# DashDial.net
KiCad netlist of a schematic drawn in EAGLE
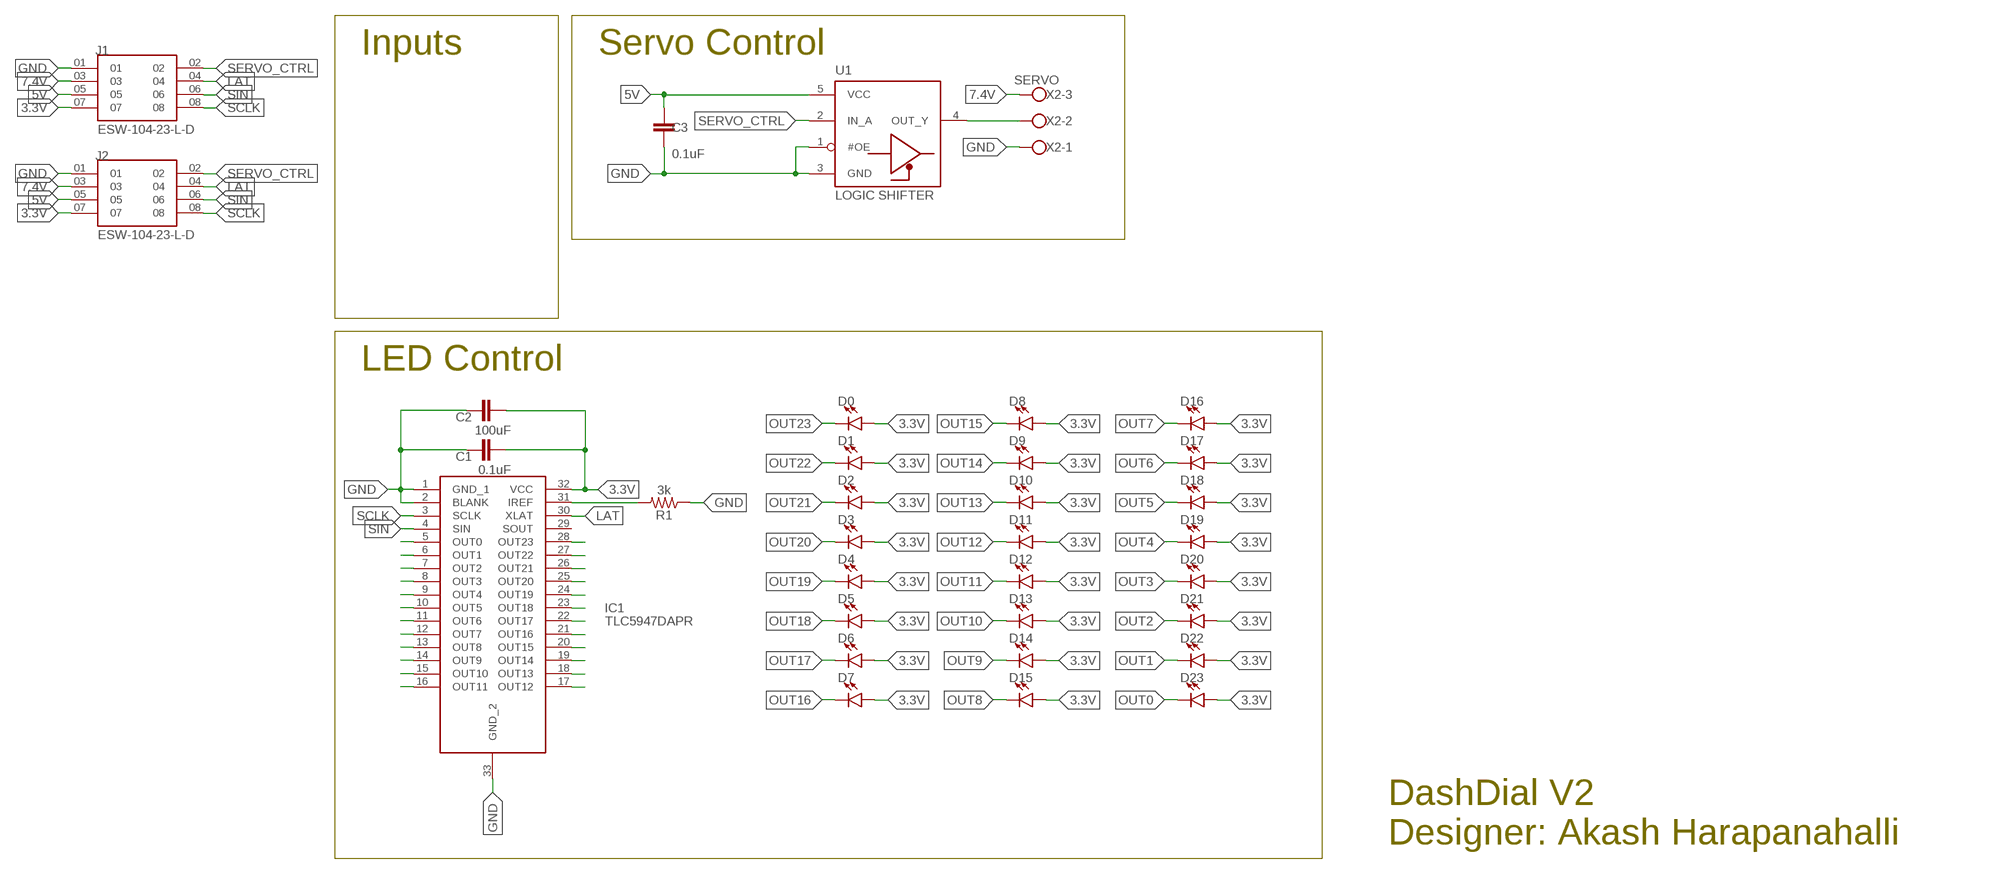
[diagram p0: schematic, sheet 1]

(export (version "E")
  (design (tool "Eeschema 10.0.6"))
  (components
    (comp (ref "C1")
      (value "0.1uF")
      (footprint "eagle-import:C0402")
      (libsource (lib "eagle-import") (part "C-EUC0402"))
    )
    (comp (ref "C2")
      (value "100uF")
      (footprint "eagle-import:C1206")
      (libsource (lib "eagle-import") (part "C-EUC1206"))
    )
    (comp (ref "C3")
      (value "0.1uF")
      (footprint "eagle-import:0603")
      (libsource (lib "eagle-import") (part "0.1UF-0603-25V-(+80/-20%)"))
    )
    (comp (ref "D0")
      (value "LED3MM")
      (footprint "eagle-import:LED_3MM")
      (libsource (lib "eagle-import") (part "LED3MM"))
    )
    (comp (ref "D1")
      (value "LED3MM")
      (footprint "eagle-import:LED_3MM")
      (libsource (lib "eagle-import") (part "LED3MM"))
    )
    (comp (ref "D2")
      (value "LED3MM")
      (footprint "eagle-import:LED_3MM")
      (libsource (lib "eagle-import") (part "LED3MM"))
    )
    (comp (ref "D3")
      (value "LED3MM")
      (footprint "eagle-import:LED_3MM")
      (libsource (lib "eagle-import") (part "LED3MM"))
    )
    (comp (ref "D4")
      (value "LED3MM")
      (footprint "eagle-import:LED_3MM")
      (libsource (lib "eagle-import") (part "LED3MM"))
    )
    (comp (ref "D5")
      (value "LED3MM")
      (footprint "eagle-import:LED_3MM")
      (libsource (lib "eagle-import") (part "LED3MM"))
    )
    (comp (ref "D6")
      (value "LED3MM")
      (footprint "eagle-import:LED_3MM")
      (libsource (lib "eagle-import") (part "LED3MM"))
    )
    (comp (ref "D7")
      (value "LED3MM")
      (footprint "eagle-import:LED_3MM")
      (libsource (lib "eagle-import") (part "LED3MM"))
    )
    (comp (ref "D8")
      (value "LED3MM")
      (footprint "eagle-import:LED_3MM")
      (libsource (lib "eagle-import") (part "LED3MM"))
    )
    (comp (ref "D9")
      (value "LED3MM")
      (footprint "eagle-import:LED_3MM")
      (libsource (lib "eagle-import") (part "LED3MM"))
    )
    (comp (ref "D10")
      (value "LED3MM")
      (footprint "eagle-import:LED_3MM")
      (libsource (lib "eagle-import") (part "LED3MM"))
    )
    (comp (ref "D11")
      (value "LED3MM")
      (footprint "eagle-import:LED_3MM")
      (libsource (lib "eagle-import") (part "LED3MM"))
    )
    (comp (ref "D12")
      (value "LED3MM")
      (footprint "eagle-import:LED_3MM")
      (libsource (lib "eagle-import") (part "LED3MM"))
    )
    (comp (ref "D13")
      (value "LED3MM")
      (footprint "eagle-import:LED_3MM")
      (libsource (lib "eagle-import") (part "LED3MM"))
    )
    (comp (ref "D14")
      (value "LED3MM")
      (footprint "eagle-import:LED_3MM")
      (libsource (lib "eagle-import") (part "LED3MM"))
    )
    (comp (ref "D15")
      (value "LED3MM")
      (footprint "eagle-import:LED_3MM")
      (libsource (lib "eagle-import") (part "LED3MM"))
    )
    (comp (ref "D16")
      (value "LED3MM")
      (footprint "eagle-import:LED_3MM")
      (libsource (lib "eagle-import") (part "LED3MM"))
    )
    (comp (ref "D17")
      (value "LED3MM")
      (footprint "eagle-import:LED_3MM")
      (libsource (lib "eagle-import") (part "LED3MM"))
    )
    (comp (ref "D18")
      (value "LED3MM")
      (footprint "eagle-import:LED_3MM")
      (libsource (lib "eagle-import") (part "LED3MM"))
    )
    (comp (ref "D19")
      (value "LED3MM")
      (footprint "eagle-import:LED_3MM")
      (libsource (lib "eagle-import") (part "LED3MM"))
    )
    (comp (ref "D20")
      (value "LED3MM")
      (footprint "eagle-import:LED_3MM")
      (libsource (lib "eagle-import") (part "LED3MM"))
    )
    (comp (ref "D21")
      (value "LED3MM")
      (footprint "eagle-import:LED_3MM")
      (libsource (lib "eagle-import") (part "LED3MM"))
    )
    (comp (ref "D22")
      (value "LED3MM")
      (footprint "eagle-import:LED_3MM")
      (libsource (lib "eagle-import") (part "LED3MM"))
    )
    (comp (ref "D23")
      (value "LED3MM")
      (footprint "eagle-import:LED_3MM")
      (libsource (lib "eagle-import") (part "LED3MM"))
    )
    (comp (ref "IC1")
      (value "TLC5947DAPR")
      (footprint "eagle-import:SOP65P810X120-33N")
      (fields (field (name "MOUSER_PART_NUMBER") "595-TLC5947DAPR"))
      (libsource (lib "eagle-import") (part "TLC5947DAPR"))
    )
    (comp (ref "J1")
      (value "ESW-104-23-L-D")
      (footprint "eagle-import:SAMTEC_ESW-104-23-L-D")
      (fields (field (name "MANUFACTURER") "Samtec Inc."))
      (libsource (lib "eagle-import") (part "ESW-104-23-L-D"))
    )
    (comp (ref "J2")
      (value "ESW-104-23-L-D")
      (footprint "eagle-import:SAMTEC_ESW-104-23-L-D")
      (fields (field (name "MANUFACTURER") "Samtec Inc."))
      (libsource (lib "eagle-import") (part "ESW-104-23-L-D"))
    )
    (comp (ref "R1")
      (value "3k")
      (footprint "eagle-import:AXIAL-0.3")
      (libsource (lib "eagle-import") (part "RESISTORAXIAL-0.3"))
    )
    (comp (ref "U1")
      (value "LOGIC SHIFTER")
      (footprint "eagle-import:SOT353")
      (fields (field (name "MF") "ON Semiconductor") (field (name "MP") "MC74VHC1GT125"))
      (libsource (lib "eagle-import") (part "MC74VHC1GT125DF"))
    )
    (comp (ref "X2")
      (value "SERVO")
      (footprint "eagle-import:W237-103")
      (fields (field (name "MPN") "237-103"))
      (libsource (lib "eagle-import") (part "W237-103"))
    )
  )
  (nets
    (net (code "1") (name "3.3V") (class "Default")
      (node (ref "C1") (pin "2") (pinfunction "2_2") (pintype "passive"))
      (node (ref "C2") (pin "2") (pinfunction "2_2") (pintype "passive"))
      (node (ref "D0") (pin "A") (pinfunction "A_A") (pintype "passive"))
      (node (ref "D1") (pin "A") (pinfunction "A_A") (pintype "passive"))
      (node (ref "D10") (pin "A") (pinfunction "A_A") (pintype "passive"))
      (node (ref "D11") (pin "A") (pinfunction "A_A") (pintype "passive"))
      (node (ref "D12") (pin "A") (pinfunction "A_A") (pintype "passive"))
      (node (ref "D13") (pin "A") (pinfunction "A_A") (pintype "passive"))
      (node (ref "D14") (pin "A") (pinfunction "A_A") (pintype "passive"))
      (node (ref "D15") (pin "A") (pinfunction "A_A") (pintype "passive"))
      (node (ref "D16") (pin "A") (pinfunction "A_A") (pintype "passive"))
      (node (ref "D17") (pin "A") (pinfunction "A_A") (pintype "passive"))
      (node (ref "D18") (pin "A") (pinfunction "A_A") (pintype "passive"))
      (node (ref "D19") (pin "A") (pinfunction "A_A") (pintype "passive"))
      (node (ref "D2") (pin "A") (pinfunction "A_A") (pintype "passive"))
      (node (ref "D20") (pin "A") (pinfunction "A_A") (pintype "passive"))
      (node (ref "D21") (pin "A") (pinfunction "A_A") (pintype "passive"))
      (node (ref "D22") (pin "A") (pinfunction "A_A") (pintype "passive"))
      (node (ref "D23") (pin "A") (pinfunction "A_A") (pintype "passive"))
      (node (ref "D3") (pin "A") (pinfunction "A_A") (pintype "passive"))
      (node (ref "D4") (pin "A") (pinfunction "A_A") (pintype "passive"))
      (node (ref "D5") (pin "A") (pinfunction "A_A") (pintype "passive"))
      (node (ref "D6") (pin "A") (pinfunction "A_A") (pintype "passive"))
      (node (ref "D7") (pin "A") (pinfunction "A_A") (pintype "passive"))
      (node (ref "D8") (pin "A") (pinfunction "A_A") (pintype "passive"))
      (node (ref "D9") (pin "A") (pinfunction "A_A") (pintype "passive"))
      (node (ref "IC1") (pin "32") (pinfunction "VCC_32") (pintype "power_in"))
      (node (ref "J1") (pin "07") (pinfunction "07_07") (pintype "passive"))
      (node (ref "J2") (pin "07") (pinfunction "07_07") (pintype "passive"))
    )
    (net (code "2") (name "5V") (class "Default")
      (node (ref "C3") (pin "1") (pinfunction "1_1") (pintype "passive"))
      (node (ref "J1") (pin "05") (pinfunction "05_05") (pintype "passive"))
      (node (ref "J2") (pin "05") (pinfunction "05_05") (pintype "passive"))
      (node (ref "U1") (pin "5") (pinfunction "VCC_5") (pintype "power_in"))
    )
    (net (code "3") (name "7.4V") (class "Default")
      (node (ref "J1") (pin "03") (pinfunction "03_03") (pintype "passive"))
      (node (ref "J2") (pin "03") (pinfunction "03_03") (pintype "passive"))
      (node (ref "X2") (pin "3") (pinfunction "KL_3") (pintype "passive"))
    )
    (net (code "4") (name "GND") (class "Default")
      (node (ref "C1") (pin "1") (pinfunction "1_1") (pintype "passive"))
      (node (ref "C2") (pin "1") (pinfunction "1_1") (pintype "passive"))
      (node (ref "C3") (pin "2") (pinfunction "2_2") (pintype "passive"))
      (node (ref "IC1") (pin "1") (pinfunction "GND_1_1") (pintype "power_in"))
      (node (ref "IC1") (pin "2") (pinfunction "BLANK_2") (pintype "input"))
      (node (ref "IC1") (pin "33") (pinfunction "GND_2_33") (pintype "power_in"))
      (node (ref "J1") (pin "01") (pinfunction "01_01") (pintype "passive"))
      (node (ref "J2") (pin "01") (pinfunction "01_01") (pintype "passive"))
      (node (ref "R1") (pin "P$1") (pinfunction "1_P$1") (pintype "passive"))
      (node (ref "U1") (pin "1") (pinfunction "#OE_1") (pintype "input"))
      (node (ref "U1") (pin "3") (pinfunction "GND_3") (pintype "power_in"))
      (node (ref "X2") (pin "1") (pinfunction "KL_1") (pintype "passive"))
    )
    (net (code "5") (name "LAT") (class "Default")
      (node (ref "IC1") (pin "30") (pinfunction "XLAT_30") (pintype "input"))
      (node (ref "J1") (pin "04") (pinfunction "04_04") (pintype "passive"))
      (node (ref "J2") (pin "04") (pinfunction "04_04") (pintype "passive"))
    )
    (net (code "6") (name "Net-(IC1-IREF)") (class "Default")
      (node (ref "IC1") (pin "31") (pinfunction "IREF_31") (pintype "input"))
      (node (ref "R1") (pin "P$2") (pinfunction "2_P$2") (pintype "passive"))
    )
    (net (code "7") (name "Net-(U1-OUT_Y)") (class "Default")
      (node (ref "U1") (pin "4") (pinfunction "OUT_Y_4") (pintype "bidirectional"))
      (node (ref "X2") (pin "2") (pinfunction "KL_2") (pintype "passive"))
    )
    (net (code "8") (name "OUT0") (class "Default")
      (node (ref "D23") (pin "K") (pinfunction "C_K") (pintype "passive"))
      (node (ref "IC1") (pin "5") (pinfunction "OUT0_5") (pintype "output"))
    )
    (net (code "9") (name "OUT1") (class "Default")
      (node (ref "D22") (pin "K") (pinfunction "C_K") (pintype "passive"))
      (node (ref "IC1") (pin "6") (pinfunction "OUT1_6") (pintype "output"))
    )
    (net (code "10") (name "OUT2") (class "Default")
      (node (ref "D21") (pin "K") (pinfunction "C_K") (pintype "passive"))
      (node (ref "IC1") (pin "7") (pinfunction "OUT2_7") (pintype "output"))
    )
    (net (code "11") (name "OUT3") (class "Default")
      (node (ref "D20") (pin "K") (pinfunction "C_K") (pintype "passive"))
      (node (ref "IC1") (pin "8") (pinfunction "OUT3_8") (pintype "output"))
    )
    (net (code "12") (name "OUT4") (class "Default")
      (node (ref "D19") (pin "K") (pinfunction "C_K") (pintype "passive"))
      (node (ref "IC1") (pin "9") (pinfunction "OUT4_9") (pintype "output"))
    )
    (net (code "13") (name "OUT5") (class "Default")
      (node (ref "D18") (pin "K") (pinfunction "C_K") (pintype "passive"))
      (node (ref "IC1") (pin "10") (pinfunction "OUT5_10") (pintype "output"))
    )
    (net (code "14") (name "OUT6") (class "Default")
      (node (ref "D17") (pin "K") (pinfunction "C_K") (pintype "passive"))
      (node (ref "IC1") (pin "11") (pinfunction "OUT6_11") (pintype "output"))
    )
    (net (code "15") (name "OUT7") (class "Default")
      (node (ref "D16") (pin "K") (pinfunction "C_K") (pintype "passive"))
      (node (ref "IC1") (pin "12") (pinfunction "OUT7_12") (pintype "output"))
    )
    (net (code "16") (name "OUT8") (class "Default")
      (node (ref "D15") (pin "K") (pinfunction "C_K") (pintype "passive"))
      (node (ref "IC1") (pin "13") (pinfunction "OUT8_13") (pintype "output"))
    )
    (net (code "17") (name "OUT9") (class "Default")
      (node (ref "D14") (pin "K") (pinfunction "C_K") (pintype "passive"))
      (node (ref "IC1") (pin "14") (pinfunction "OUT9_14") (pintype "output"))
    )
    (net (code "18") (name "OUT10") (class "Default")
      (node (ref "D13") (pin "K") (pinfunction "C_K") (pintype "passive"))
      (node (ref "IC1") (pin "15") (pinfunction "OUT10_15") (pintype "output"))
    )
    (net (code "19") (name "OUT11") (class "Default")
      (node (ref "D12") (pin "K") (pinfunction "C_K") (pintype "passive"))
      (node (ref "IC1") (pin "16") (pinfunction "OUT11_16") (pintype "output"))
    )
    (net (code "20") (name "OUT12") (class "Default")
      (node (ref "D11") (pin "K") (pinfunction "C_K") (pintype "passive"))
      (node (ref "IC1") (pin "17") (pinfunction "OUT12_17") (pintype "output"))
    )
    (net (code "21") (name "OUT13") (class "Default")
      (node (ref "D10") (pin "K") (pinfunction "C_K") (pintype "passive"))
      (node (ref "IC1") (pin "18") (pinfunction "OUT13_18") (pintype "output"))
    )
    (net (code "22") (name "OUT14") (class "Default")
      (node (ref "D9") (pin "K") (pinfunction "C_K") (pintype "passive"))
      (node (ref "IC1") (pin "19") (pinfunction "OUT14_19") (pintype "output"))
    )
    (net (code "23") (name "OUT15") (class "Default")
      (node (ref "D8") (pin "K") (pinfunction "C_K") (pintype "passive"))
      (node (ref "IC1") (pin "20") (pinfunction "OUT15_20") (pintype "output"))
    )
    (net (code "24") (name "OUT16") (class "Default")
      (node (ref "D7") (pin "K") (pinfunction "C_K") (pintype "passive"))
      (node (ref "IC1") (pin "21") (pinfunction "OUT16_21") (pintype "output"))
    )
    (net (code "25") (name "OUT17") (class "Default")
      (node (ref "D6") (pin "K") (pinfunction "C_K") (pintype "passive"))
      (node (ref "IC1") (pin "22") (pinfunction "OUT17_22") (pintype "output"))
    )
    (net (code "26") (name "OUT18") (class "Default")
      (node (ref "D5") (pin "K") (pinfunction "C_K") (pintype "passive"))
      (node (ref "IC1") (pin "23") (pinfunction "OUT18_23") (pintype "output"))
    )
    (net (code "27") (name "OUT19") (class "Default")
      (node (ref "D4") (pin "K") (pinfunction "C_K") (pintype "passive"))
      (node (ref "IC1") (pin "24") (pinfunction "OUT19_24") (pintype "output"))
    )
    (net (code "28") (name "OUT20") (class "Default")
      (node (ref "D3") (pin "K") (pinfunction "C_K") (pintype "passive"))
      (node (ref "IC1") (pin "25") (pinfunction "OUT20_25") (pintype "output"))
    )
    (net (code "29") (name "OUT21") (class "Default")
      (node (ref "D2") (pin "K") (pinfunction "C_K") (pintype "passive"))
      (node (ref "IC1") (pin "26") (pinfunction "OUT21_26") (pintype "output"))
    )
    (net (code "30") (name "OUT22") (class "Default")
      (node (ref "D1") (pin "K") (pinfunction "C_K") (pintype "passive"))
      (node (ref "IC1") (pin "27") (pinfunction "OUT22_27") (pintype "output"))
    )
    (net (code "31") (name "OUT23") (class "Default")
      (node (ref "D0") (pin "K") (pinfunction "C_K") (pintype "passive"))
      (node (ref "IC1") (pin "28") (pinfunction "OUT23_28") (pintype "output"))
    )
    (net (code "32") (name "SCLK") (class "Default")
      (node (ref "IC1") (pin "3") (pinfunction "SCLK_3") (pintype "input"))
      (node (ref "J1") (pin "08") (pinfunction "08_08") (pintype "passive"))
      (node (ref "J2") (pin "08") (pinfunction "08_08") (pintype "passive"))
    )
    (net (code "33") (name "SERVO_CTRL") (class "Default")
      (node (ref "J1") (pin "02") (pinfunction "02_02") (pintype "passive"))
      (node (ref "J2") (pin "02") (pinfunction "02_02") (pintype "passive"))
      (node (ref "U1") (pin "2") (pinfunction "IN_A_2") (pintype "bidirectional"))
    )
    (net (code "34") (name "SIN") (class "Default")
      (node (ref "IC1") (pin "4") (pinfunction "SIN_4") (pintype "input"))
      (node (ref "J1") (pin "06") (pinfunction "06_06") (pintype "passive"))
      (node (ref "J2") (pin "06") (pinfunction "06_06") (pintype "passive"))
    )
    (net (code "35") (name "unconnected-(IC1-SOUT-Pad29)") (class "Default")
      (node (ref "IC1") (pin "29") (pinfunction "SOUT_29") (pintype "output"))
    )
  )
)
